# 02_Top_Level.net
KiCad netlist of a schematic drawn in Altium Designer
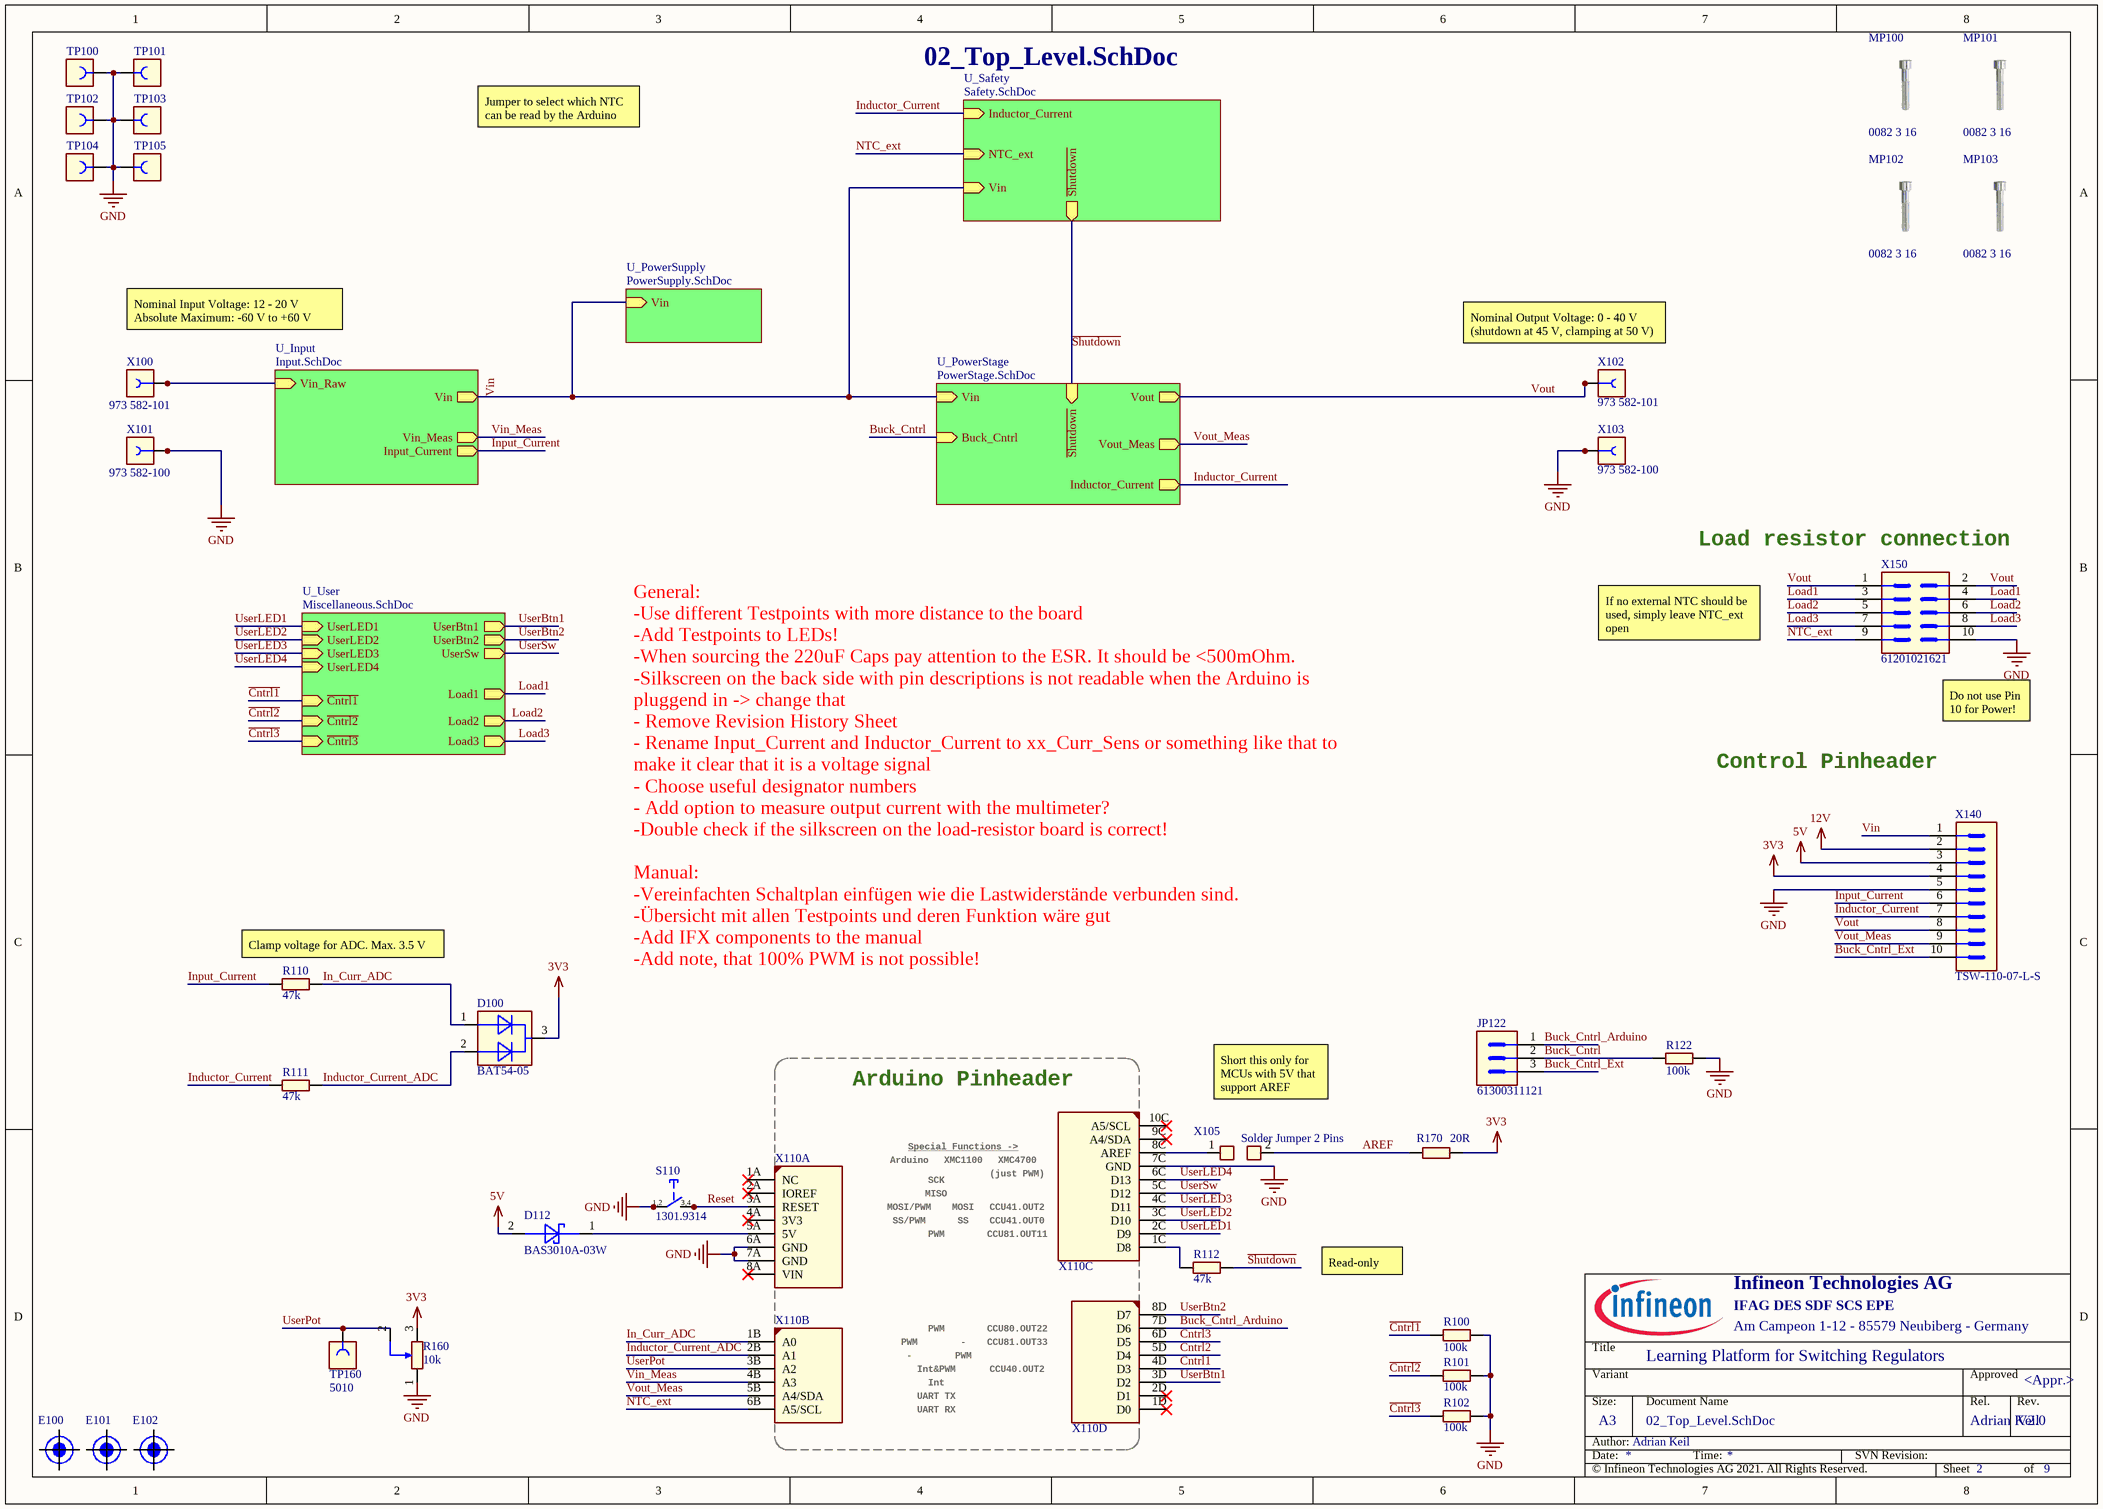
[diagram p0: 02_Top_Level.SchDoc]

(export (version "E")
  (design (tool "Eeschema 10.0.6"))
  (components
    (comp (ref "D100")
      (value "BAT54-05")
      (footprint "SOT95P240X110-3N-1-V")
      (description "Silicon Schottky Diode, LS(nH) 1.8, VR 30V")
      (fields
        (field (name "LEGACY PARTNUMBER") "IFX01401370")
        (field (name "MANUFACTURER") "Infineon Technologies")
      )
      (libsource (lib "PCBLibraryData") (part "d_dual_a1a2c3_3p"))
    )
    (comp (ref "D112")
      (value "BAS3010A-03W")
      (footprint "SOD2513X110N")
      (description "Medium Power AF Schottky Diode")
      (fields
        (field (name "LEGACY PARTNUMBER") "IFX01400145")
        (field (name "MANUFACTURER") "Infineon Technologies")
      )
      (libsource (lib "PCBLibraryData") (part "d_schottky_a"))
    )
    (comp (ref "E100")
      (value "~")
      (footprint "fiducial")
      (description "Fiducial Mark")
      (fields
        (field (name "LEGACY PARTNUMBER") "MEC10000008")
        (field (name "MANUFACTURER") "Infineon Technologies")
      )
      (libsource (lib "PCBLibraryData") (part "fiducial"))
    )
    (comp (ref "E101")
      (value "~")
      (footprint "fiducial")
      (description "Fiducial Mark")
      (fields
        (field (name "LEGACY PARTNUMBER") "MEC10000008")
        (field (name "MANUFACTURER") "Infineon Technologies")
      )
      (libsource (lib "PCBLibraryData") (part "fiducial"))
    )
    (comp (ref "E102")
      (value "~")
      (footprint "fiducial")
      (description "Fiducial Mark")
      (fields
        (field (name "LEGACY PARTNUMBER") "MEC10000008")
        (field (name "MANUFACTURER") "Infineon Technologies")
      )
      (libsource (lib "PCBLibraryData") (part "fiducial"))
    )
    (comp (ref "JP122")
      (value "61300311121")
      (footprint "CON-M-THT-61300311121")
      (description "WR-PHD Pin Header")
      (fields (field (name "MANUFACTURER") "Wurth Elektronik"))
      (libsource (lib "PCBLibraryData") (part "Header 3"))
    )
    (comp (ref "MP100")
      (value "0082 3 16")
      (footprint "SCREW_0082 3 16_NPTH")
      (description "Cheese Head Screw With Hexagon Socket, DIN 912 (ISO 4762), M3, 16mm length")
      (fields
        (field (name "LEGACY PARTNUMBER") "MEC10000167")
        (field (name "MANUFACTURER") "Wurth Elektronik")
      )
      (libsource (lib "PCBLibraryData") (part "Screw_0082 3 16"))
    )
    (comp (ref "MP101")
      (value "0082 3 16")
      (footprint "SCREW_0082 3 16_NPTH")
      (description "Cheese Head Screw With Hexagon Socket, DIN 912 (ISO 4762), M3, 16mm length")
      (fields
        (field (name "LEGACY PARTNUMBER") "MEC10000167")
        (field (name "MANUFACTURER") "Wurth Elektronik")
      )
      (libsource (lib "PCBLibraryData") (part "Screw_0082 3 16"))
    )
    (comp (ref "MP102")
      (value "0082 3 16")
      (footprint "SCREW_0082 3 16_NPTH")
      (description "Cheese Head Screw With Hexagon Socket, DIN 912 (ISO 4762), M3, 16mm length")
      (fields
        (field (name "LEGACY PARTNUMBER") "MEC10000167")
        (field (name "MANUFACTURER") "Wurth Elektronik")
      )
      (libsource (lib "PCBLibraryData") (part "Screw_0082 3 16"))
    )
    (comp (ref "MP103")
      (value "0082 3 16")
      (footprint "SCREW_0082 3 16_NPTH")
      (description "Cheese Head Screw With Hexagon Socket, DIN 912 (ISO 4762), M3, 16mm length")
      (fields
        (field (name "LEGACY PARTNUMBER") "MEC10000167")
        (field (name "MANUFACTURER") "Wurth Elektronik")
      )
      (libsource (lib "PCBLibraryData") (part "Screw_0082 3 16"))
    )
    (comp (ref "R100")
      (value "100k")
      (footprint "RESC1508X60N")
      (fields (field (name "MANUFACTURER") "Bourns"))
      (libsource (lib "") (part "RES-SGL-STD-02P_00000006_1"))
    )
    (comp (ref "R101")
      (value "100k")
      (footprint "RESC1508X60N")
      (fields (field (name "MANUFACTURER") "Bourns"))
      (libsource (lib "") (part "RES-SGL-STD-02P_00000006_1"))
    )
    (comp (ref "R102")
      (value "100k")
      (footprint "RESC1508X60N")
      (fields (field (name "MANUFACTURER") "Bourns"))
      (libsource (lib "") (part "RES-SGL-STD-02P_00000006_1"))
    )
    (comp (ref "R110")
      (value "47k")
      (footprint "RESC1609X50N")
      (description "RES / STD / 47k / 100mW / 1% / 100ppm/K / -55°C to 155°C / 0603 / SMD / -")
      (fields (field (name "LEGACY PARTNUMBER") "RES01801333") (field (name "MANUFACTURER") "Vishay"))
      (libsource (lib "PCBLibraryData") (part "RES-SGL-STD-02P_00000006"))
    )
    (comp (ref "R111")
      (value "47k")
      (footprint "RESC1609X50N")
      (description "RES / STD / 47k / 100mW / 1% / 100ppm/K / -55°C to 155°C / 0603 / SMD / -")
      (fields (field (name "LEGACY PARTNUMBER") "RES01801333") (field (name "MANUFACTURER") "Vishay"))
      (libsource (lib "PCBLibraryData") (part "RES-SGL-STD-02P_00000006"))
    )
    (comp (ref "R112")
      (value "47k")
      (footprint "RESC1609X50N")
      (description "RES / STD / 47k / 100mW / 1% / 100ppm/K / -55°C to 155°C / 0603 / SMD / -")
      (fields (field (name "LEGACY PARTNUMBER") "RES01801333") (field (name "MANUFACTURER") "Vishay"))
      (libsource (lib "PCBLibraryData") (part "RES-SGL-STD-02P_00000006"))
    )
    (comp (ref "R122")
      (value "100k")
      (footprint "RESC1508X60N")
      (fields (field (name "MANUFACTURER") "Bourns"))
      (libsource (lib "") (part "RES-SGL-STD-02P_00000006_1"))
    )
    (comp (ref "R160")
      (value "10k")
      (footprint "POT-SMD-TC42X-2")
      (fields (field (name "MANUFACTURER") "Bourns"))
      (libsource (lib "PCBLibraryData") (part "RES-SGL-VAR-03P_00000026"))
    )
    (comp (ref "R170")
      (value "20R")
      (footprint "RESC1609X50N")
      (description "RES / STD / 20R / 100mW / 1% / 100ppm/K / -55°C to 155°C / 0603 / SMD / -")
      (fields (field (name "LEGACY PARTNUMBER") "RES01800947") (field (name "MANUFACTURER") "Vishay"))
      (libsource (lib "") (part "RES-SGL-STD-02P_00000006_1"))
    )
    (comp (ref "S110")
      (value "1301.9314")
      (footprint "SW-SMD-1301.9314")
      (description "Pushbutton Tactile Switch, Single Pole Single Throw, 4 Pins")
      (fields (field (name "LEGACY PARTNUMBER") "CON01500305") (field (name "MANUFACTURER") "Schurter"))
      (libsource (lib "PCBLibraryData") (part "sw_sr_no12_34_4p"))
    )
    (comp (ref "TP100")
      (value "5011")
      (footprint "CON-THT-TP-5011")
      (description "PC Test Point-Multipurpose THT, Black")
      (fields
        (field (name "LEGACY PARTNUMBER") "CON01500530")
        (field (name "MANUFACTURER") "Keystone Electronics Corp.")
      )
      (libsource (lib "") (part "connector_1_f_1"))
    )
    (comp (ref "TP101")
      (value "5011")
      (footprint "CON-THT-TP-5011")
      (description "PC Test Point-Multipurpose THT, Black")
      (fields
        (field (name "LEGACY PARTNUMBER") "CON01500530")
        (field (name "MANUFACTURER") "Keystone Electronics Corp.")
      )
      (libsource (lib "") (part "connector_1_f_2"))
    )
    (comp (ref "TP102")
      (value "5011")
      (footprint "CON-THT-TP-5011")
      (description "PC Test Point-Multipurpose THT, Black")
      (fields
        (field (name "LEGACY PARTNUMBER") "CON01500530")
        (field (name "MANUFACTURER") "Keystone Electronics Corp.")
      )
      (libsource (lib "") (part "connector_1_f_1"))
    )
    (comp (ref "TP103")
      (value "5011")
      (footprint "CON-THT-TP-5011")
      (description "PC Test Point-Multipurpose THT, Black")
      (fields
        (field (name "LEGACY PARTNUMBER") "CON01500530")
        (field (name "MANUFACTURER") "Keystone Electronics Corp.")
      )
      (libsource (lib "") (part "connector_1_f_2"))
    )
    (comp (ref "TP104")
      (value "5011")
      (footprint "CON-THT-TP-5011")
      (description "PC Test Point-Multipurpose THT, Black")
      (fields
        (field (name "LEGACY PARTNUMBER") "CON01500530")
        (field (name "MANUFACTURER") "Keystone Electronics Corp.")
      )
      (libsource (lib "") (part "connector_1_f_1"))
    )
    (comp (ref "TP105")
      (value "5011")
      (footprint "CON-THT-TP-5011")
      (description "PC Test Point-Multipurpose THT, Black")
      (fields
        (field (name "LEGACY PARTNUMBER") "CON01500530")
        (field (name "MANUFACTURER") "Keystone Electronics Corp.")
      )
      (libsource (lib "") (part "connector_1_f_2"))
    )
    (comp (ref "TP160")
      (value "5010")
      (footprint "CON-THT-TP-5010")
      (description "PC Test Point-Multipurpose THT, Red")
      (fields
        (field (name "LEGACY PARTNUMBER") "CON01500529")
        (field (name "MANUFACTURER") "Keystone Electronics Corp.")
      )
      (libsource (lib "PCBLibraryData") (part "connector_1_f"))
    )
    (comp (ref "X100")
      (value "973 582-101")
      (footprint "CON-THT-973 582- 101")
      (description "Banana Socket, Red, 17.5mm Pitch")
      (fields
        (field (name "LEGACY PARTNUMBER") "CON01500041")
        (field (name "MANUFACTURER") "Hirschmann Test & Measurement")
      )
      (libsource (lib "") (part "soc_banana_2p_1"))
    )
    (comp (ref "X101")
      (value "973 582-100")
      (footprint "CON-THT-973 582- 100")
      (description "Banana Socket, black, 17.5mm Pitch")
      (fields
        (field (name "LEGACY PARTNUMBER") "CON01500045")
        (field (name "MANUFACTURER") "Hirschmann Test & Measurement")
      )
      (libsource (lib "") (part "soc_banana_2p_1"))
    )
    (comp (ref "X102")
      (value "973 582-101")
      (footprint "CON-THT-973 582- 101")
      (description "Banana Socket, Red, 17.5mm Pitch")
      (fields
        (field (name "LEGACY PARTNUMBER") "CON01500041")
        (field (name "MANUFACTURER") "Hirschmann Test & Measurement")
      )
      (libsource (lib "PCBLibraryData") (part "soc_banana_2p"))
    )
    (comp (ref "X103")
      (value "973 582-100")
      (footprint "CON-THT-973 582- 100")
      (description "Banana Socket, black, 17.5mm Pitch")
      (fields
        (field (name "LEGACY PARTNUMBER") "CON01500045")
        (field (name "MANUFACTURER") "Hirschmann Test & Measurement")
      )
      (libsource (lib "PCBLibraryData") (part "soc_banana_2p"))
    )
    (comp (ref "X105")
      (value "Solder Jumper 2 Pins")
      (footprint "SOLDER_BRIDGE_0.7X1.299PAD")
      (fields
        (field (name "LEGACY PARTNUMBER") "CON01500959")
        (field (name "MANUFACTURER") "Infineon Technologies")
      )
      (libsource (lib "PCBLibraryData") (part "SJP_2P"))
    )
    (comp (ref "X110")
      (value "Arduino-Uno")
      (footprint "Arduino-Uno")
      (description "Arduino Uno is a microcontroller board based on the ATmega328P")
      (fields (field (name "MANUFACTURER") "Infineon Technologies"))
      (libsource (lib "PCBLibraryData") (part "Arduino-Uno"))
    )
    (comp (ref "X140")
      (value "TSW-110-07-L-S")
      (footprint "CON-M-THT-TSW-110-07-L-S")
      (description "Through hole .025 SQ Post Header, 2.54mm pitch, 10 pin, vertical, single row")
      (fields (field (name "LEGACY PARTNUMBER") "CON01500578") (field (name "MANUFACTURER") "Samtec"))
      (libsource (lib "PCBLibraryData") (part "Header 10"))
    )
    (comp (ref "X150")
      (value "61201021621")
      (footprint "CON-M-THT-61201021621")
      (description "WR-BHD Male Box Header, 2.54mm pitch, 10 pin, Vertical, Double row")
      (fields (field (name "MANUFACTURER") "Wurth Elektronik"))
      (libsource (lib "PCBLibraryData") (part "Header 5X2"))
    )
  )
  (nets
    (net (code "1") (name "/AREF") (class "Default")
      (node (ref "R170") (pin "1") (pinfunction "1_1") (pintype "passive"))
      (node (ref "X105") (pin "2") (pinfunction "2_2") (pintype "passive"))
    )
    (net (code "2") (name "/Buck_Cntrl") (class "Default")
      (node (ref "JP122") (pin "2") (pinfunction "2_2") (pintype "passive"))
      (node (ref "R122") (pin "1") (pinfunction "1_1") (pintype "passive"))
    )
    (net (code "3") (name "/Buck_Cntrl_Arduino") (class "Default")
      (node (ref "JP122") (pin "1") (pinfunction "1_1") (pintype "passive"))
      (node (ref "X110") (pin "7D") (pinfunction "D6_7D") (pintype "passive"))
    )
    (net (code "4") (name "/Buck_Cntrl_Ext") (class "Default")
      (node (ref "JP122") (pin "3") (pinfunction "3_3") (pintype "passive"))
      (node (ref "X140") (pin "10") (pinfunction "10_10") (pintype "passive"))
    )
    (net (code "5") (name "/Cntrl1") (class "Default")
      (node (ref "R100") (pin "1") (pinfunction "1_1") (pintype "passive"))
      (node (ref "X110") (pin "4D") (pinfunction "D3_4D") (pintype "passive"))
    )
    (net (code "6") (name "/Cntrl2") (class "Default")
      (node (ref "R101") (pin "1") (pinfunction "1_1") (pintype "passive"))
      (node (ref "X110") (pin "5D") (pinfunction "D4_5D") (pintype "passive"))
    )
    (net (code "7") (name "/Cntrl3") (class "Default")
      (node (ref "R102") (pin "1") (pinfunction "1_1") (pintype "passive"))
      (node (ref "X110") (pin "6D") (pinfunction "D5_6D") (pintype "passive"))
    )
    (net (code "8") (name "/In_Curr_ADC") (class "Default")
      (node (ref "D100") (pin "1") (pinfunction "ANODE_1_1") (pintype "passive"))
      (node (ref "R110") (pin "1") (pinfunction "1_1") (pintype "passive"))
      (node (ref "X110") (pin "1B") (pinfunction "A0_1B") (pintype "passive"))
    )
    (net (code "9") (name "/Inductor_Current") (class "Default")
      (node (ref "R111") (pin "2") (pinfunction "2_2") (pintype "passive"))
      (node (ref "X140") (pin "7") (pinfunction "7_7") (pintype "passive"))
    )
    (net (code "10") (name "/Inductor_Current_ADC") (class "Default")
      (node (ref "D100") (pin "2") (pinfunction "ANODE_2_2") (pintype "passive"))
      (node (ref "R111") (pin "1") (pinfunction "1_1") (pintype "passive"))
      (node (ref "X110") (pin "2B") (pinfunction "A1_2B") (pintype "passive"))
    )
    (net (code "11") (name "/Input_Current") (class "Default")
      (node (ref "R110") (pin "2") (pinfunction "2_2") (pintype "passive"))
      (node (ref "X140") (pin "6") (pinfunction "6_6") (pintype "passive"))
    )
    (net (code "12") (name "/Load1") (class "Default")
      (node (ref "X150") (pin "3") (pinfunction "3_3") (pintype "passive"))
      (node (ref "X150") (pin "4") (pinfunction "4_4") (pintype "passive"))
    )
    (net (code "13") (name "/Load2") (class "Default")
      (node (ref "X150") (pin "5") (pinfunction "5_5") (pintype "passive"))
      (node (ref "X150") (pin "6") (pinfunction "6_6") (pintype "passive"))
    )
    (net (code "14") (name "/Load3") (class "Default")
      (node (ref "X150") (pin "7") (pinfunction "7_7") (pintype "passive"))
      (node (ref "X150") (pin "8") (pinfunction "8_8") (pintype "passive"))
    )
    (net (code "15") (name "/NTC_ext") (class "Default")
      (node (ref "X110") (pin "6B") (pinfunction "A5/SCL_6B") (pintype "passive"))
      (node (ref "X150") (pin "9") (pinfunction "9_9") (pintype "passive"))
    )
    (net (code "16") (name "/Reset") (class "Default")
      (node (ref "S110") (pin "3") (pinfunction "3_3") (pintype "passive"))
      (node (ref "S110") (pin "4") (pinfunction "4_4") (pintype "passive"))
      (node (ref "X110") (pin "3A") (pinfunction "RESET_3A") (pintype "passive"))
    )
    (net (code "17") (name "/Shutdown") (class "Default")
      (node (ref "R112") (pin "1") (pinfunction "1_1") (pintype "passive"))
    )
    (net (code "18") (name "/UserBtn1") (class "Default")
      (node (ref "X110") (pin "3D") (pinfunction "D2_3D") (pintype "passive"))
    )
    (net (code "19") (name "/UserBtn2") (class "Default")
      (node (ref "X110") (pin "8D") (pinfunction "D7_8D") (pintype "passive"))
    )
    (net (code "20") (name "/UserLED1") (class "Default")
      (node (ref "X110") (pin "2C") (pinfunction "D9_2C") (pintype "passive"))
    )
    (net (code "21") (name "/UserLED2") (class "Default")
      (node (ref "X110") (pin "3C") (pinfunction "D10_3C") (pintype "passive"))
    )
    (net (code "22") (name "/UserLED3") (class "Default")
      (node (ref "X110") (pin "4C") (pinfunction "D11_4C") (pintype "passive"))
    )
    (net (code "23") (name "/UserLED4") (class "Default")
      (node (ref "X110") (pin "6C") (pinfunction "D13_6C") (pintype "passive"))
    )
    (net (code "24") (name "/UserPot") (class "Default")
      (node (ref "R160") (pin "2") (pinfunction "2_2") (pintype "passive"))
      (node (ref "TP160") (pin "1") (pinfunction "1_1") (pintype "passive"))
      (node (ref "X110") (pin "3B") (pinfunction "A2_3B") (pintype "passive"))
    )
    (net (code "25") (name "/UserSw") (class "Default")
      (node (ref "X110") (pin "5C") (pinfunction "D12_5C") (pintype "passive"))
    )
    (net (code "26") (name "/Vin") (class "Default")
      (node (ref "X140") (pin "1") (pinfunction "1_1") (pintype "passive"))
    )
    (net (code "27") (name "/Vin_Meas") (class "Default")
      (node (ref "X110") (pin "4B") (pinfunction "A3_4B") (pintype "passive"))
    )
    (net (code "28") (name "/Vin_Raw") (class "Default")
      (node (ref "X100") (pin "1") (pinfunction "1_1") (pintype "passive"))
      (node (ref "X100") (pin "2") (pinfunction "2_2") (pintype "passive"))
    )
    (net (code "29") (name "/Vout") (class "Default")
      (node (ref "X102") (pin "1") (pinfunction "1_1") (pintype "passive"))
      (node (ref "X102") (pin "2") (pinfunction "2_2") (pintype "passive"))
      (node (ref "X140") (pin "8") (pinfunction "8_8") (pintype "passive"))
      (node (ref "X150") (pin "1") (pinfunction "1_1") (pintype "passive"))
      (node (ref "X150") (pin "2") (pinfunction "2_2") (pintype "passive"))
    )
    (net (code "30") (name "/Vout_Meas") (class "Default")
      (node (ref "X110") (pin "5B") (pinfunction "A4/SDA_5B") (pintype "passive"))
      (node (ref "X140") (pin "9") (pinfunction "9_9") (pintype "passive"))
    )
    (net (code "31") (name "3V3") (class "Default")
      (node (ref "D100") (pin "3") (pinfunction "CATHODE_3") (pintype "passive"))
      (node (ref "R160") (pin "3") (pinfunction "3_3") (pintype "passive"))
      (node (ref "R170") (pin "2") (pinfunction "2_2") (pintype "passive"))
      (node (ref "X140") (pin "4") (pinfunction "4_4") (pintype "passive"))
    )
    (net (code "32") (name "5V") (class "Default")
      (node (ref "D112") (pin "2") (pinfunction "Anode_2") (pintype "passive"))
      (node (ref "X140") (pin "3") (pinfunction "3_3") (pintype "passive"))
    )
    (net (code "33") (name "12V") (class "Default")
      (node (ref "X140") (pin "2") (pinfunction "2_2") (pintype "passive"))
    )
    (net (code "34") (name "GND") (class "Default")
      (node (ref "R100") (pin "2") (pinfunction "2_2") (pintype "passive"))
      (node (ref "R101") (pin "2") (pinfunction "2_2") (pintype "passive"))
      (node (ref "R102") (pin "2") (pinfunction "2_2") (pintype "passive"))
      (node (ref "R122") (pin "2") (pinfunction "2_2") (pintype "passive"))
      (node (ref "R160") (pin "1") (pinfunction "1_1") (pintype "passive"))
      (node (ref "S110") (pin "1") (pinfunction "1_1") (pintype "passive"))
      (node (ref "S110") (pin "2") (pinfunction "2_2") (pintype "passive"))
      (node (ref "TP100") (pin "1") (pinfunction "1_1") (pintype "passive"))
      (node (ref "TP101") (pin "1") (pinfunction "1_1") (pintype "passive"))
      (node (ref "TP102") (pin "1") (pinfunction "1_1") (pintype "passive"))
      (node (ref "TP103") (pin "1") (pinfunction "1_1") (pintype "passive"))
      (node (ref "TP104") (pin "1") (pinfunction "1_1") (pintype "passive"))
      (node (ref "TP105") (pin "1") (pinfunction "1_1") (pintype "passive"))
      (node (ref "X101") (pin "1") (pinfunction "1_1") (pintype "passive"))
      (node (ref "X101") (pin "2") (pinfunction "2_2") (pintype "passive"))
      (node (ref "X103") (pin "1") (pinfunction "1_1") (pintype "passive"))
      (node (ref "X103") (pin "2") (pinfunction "2_2") (pintype "passive"))
      (node (ref "X110") (pin "6A") (pinfunction "GND_6A") (pintype "passive"))
      (node (ref "X110") (pin "7A") (pinfunction "GND_7A") (pintype "passive"))
      (node (ref "X110") (pin "7C") (pinfunction "GND_7C") (pintype "passive"))
      (node (ref "X140") (pin "5") (pinfunction "5_5") (pintype "passive"))
      (node (ref "X150") (pin "10") (pinfunction "10_10") (pintype "passive"))
    )
    (net (code "35") (name "Net-(D112-Cathode)") (class "Default")
      (node (ref "D112") (pin "1") (pinfunction "Cathode_1") (pintype "passive"))
      (node (ref "X110") (pin "5A") (pinfunction "5V_5A") (pintype "passive"))
    )
    (net (code "36") (name "Net-(X110C-AREF)") (class "Default")
      (node (ref "X105") (pin "1") (pinfunction "1_1") (pintype "passive"))
      (node (ref "X110") (pin "8C") (pinfunction "AREF_8C") (pintype "passive"))
    )
    (net (code "37") (name "Net-(X110C-D8)") (class "Default")
      (node (ref "R112") (pin "2") (pinfunction "2_2") (pintype "passive"))
      (node (ref "X110") (pin "1C") (pinfunction "D8_1C") (pintype "passive"))
    )
    (net (code "38") (name "unconnected-(E100-Pad1)") (class "Default")
      (node (ref "E100") (pin "1") (pinfunction "1_1") (pintype "passive"))
    )
    (net (code "39") (name "unconnected-(E101-Pad1)") (class "Default")
      (node (ref "E101") (pin "1") (pinfunction "1_1") (pintype "passive"))
    )
    (net (code "40") (name "unconnected-(E102-Pad1)") (class "Default")
      (node (ref "E102") (pin "1") (pinfunction "1_1") (pintype "passive"))
    )
    (net (code "41") (name "unconnected-(X110A-3V3-Pad4A)") (class "Default")
      (node (ref "X110") (pin "4A") (pinfunction "3V3_4A") (pintype "passive+no_connect"))
    )
    (net (code "42") (name "unconnected-(X110A-IOREF-Pad2A)") (class "Default")
      (node (ref "X110") (pin "2A") (pinfunction "IOREF_2A") (pintype "passive+no_connect"))
    )
    (net (code "43") (name "unconnected-(X110A-NC-Pad1A)") (class "Default")
      (node (ref "X110") (pin "1A") (pinfunction "NC_1A") (pintype "passive+no_connect"))
    )
    (net (code "44") (name "unconnected-(X110A-VIN-Pad8A)") (class "Default")
      (node (ref "X110") (pin "8A") (pinfunction "VIN_8A") (pintype "passive+no_connect"))
    )
    (net (code "45") (name "unconnected-(X110C-A4{slash}SDA-Pad9C)") (class "Default")
      (node (ref "X110") (pin "9C") (pinfunction "A4/SDA_9C") (pintype "passive+no_connect"))
    )
    (net (code "46") (name "unconnected-(X110C-A5{slash}SCL-Pad10C)") (class "Default")
      (node (ref "X110") (pin "10C") (pinfunction "A5/SCL_10C") (pintype "passive+no_connect"))
    )
    (net (code "47") (name "unconnected-(X110D-D0-Pad1D)") (class "Default")
      (node (ref "X110") (pin "1D") (pinfunction "D0_1D") (pintype "passive+no_connect"))
    )
    (net (code "48") (name "unconnected-(X110D-D1-Pad2D)") (class "Default")
      (node (ref "X110") (pin "2D") (pinfunction "D1_2D") (pintype "passive+no_connect"))
    )
  )
)
